# SCH_styresystemer_2026-04-27.net
KiCad netlist of a schematic drawn in EasyEDA
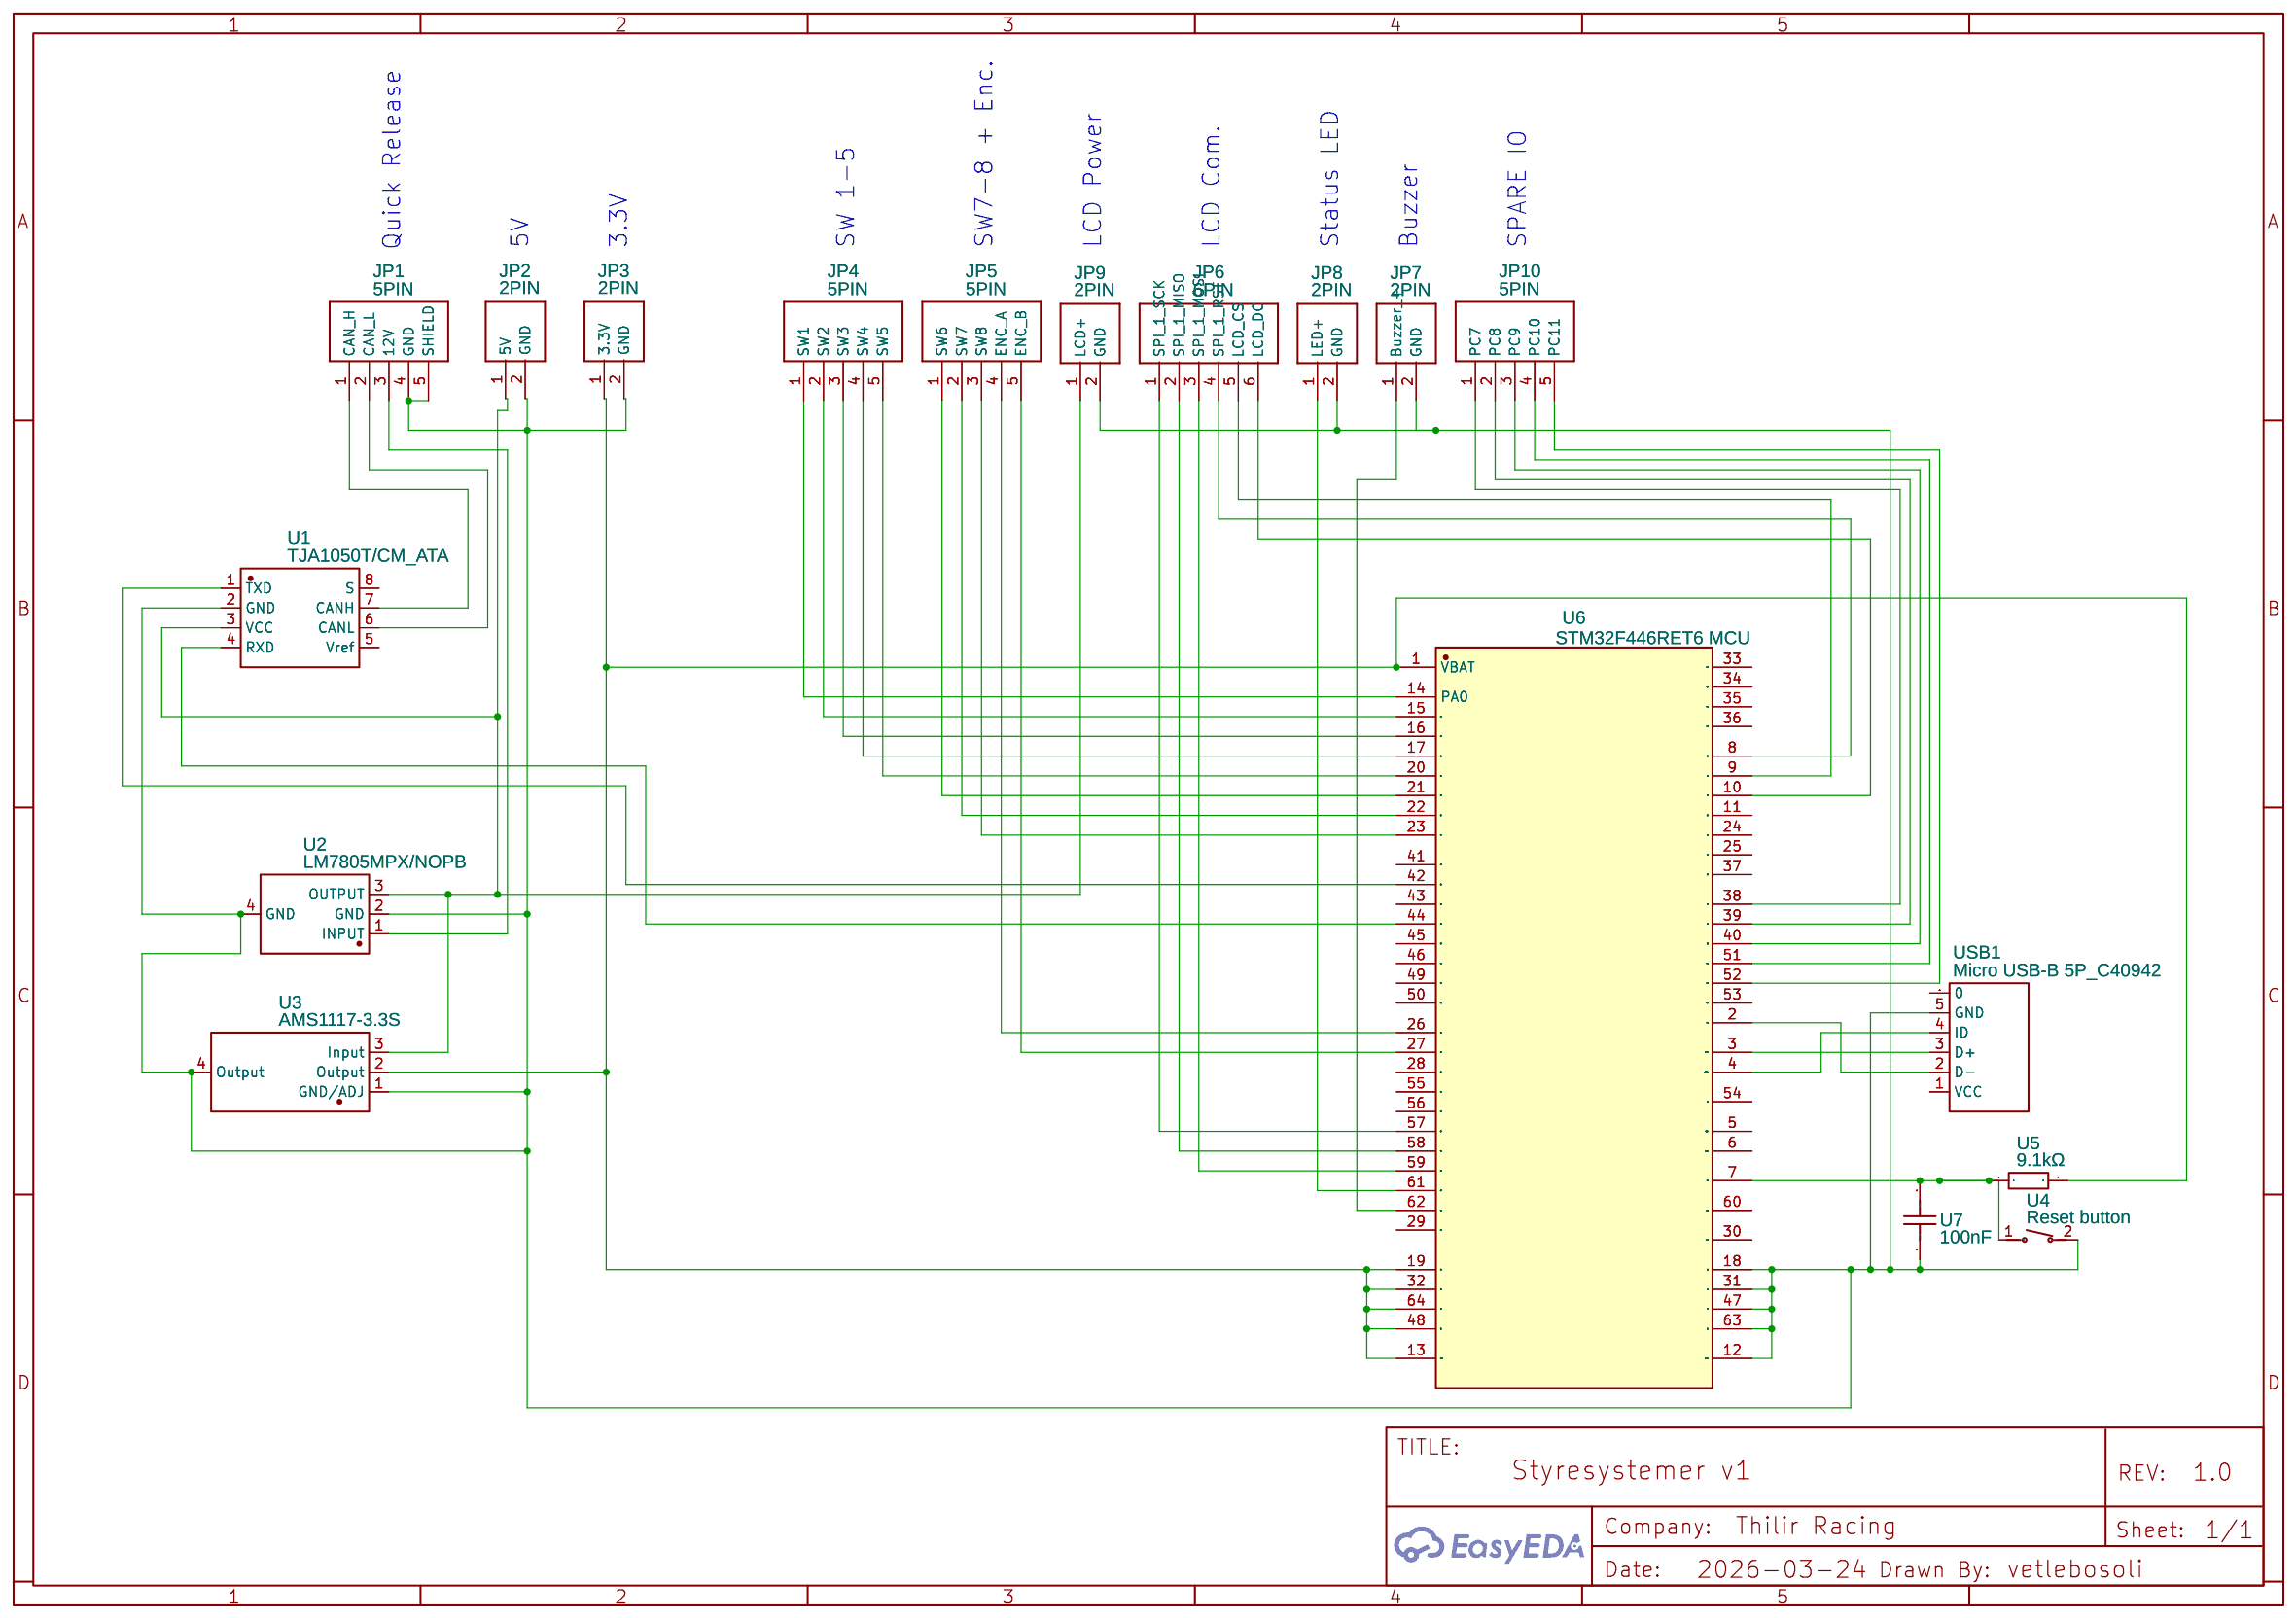
[diagram p0: schematic sheet]

(export (version "E")
  (design (tool "Eeschema 10.0.6"))
  (components
    (comp (ref "JP1") (value "5PIN") (libsource (lib "") (part "5PIN")))
    (comp (ref "JP2") (value "2PIN") (libsource (lib "") (part "2PIN_2")))
    (comp (ref "JP3") (value "2PIN") (libsource (lib "") (part "2PIN_4")))
    (comp (ref "JP4") (value "5PIN") (libsource (lib "") (part "5PIN_1")))
    (comp (ref "JP5") (value "5PIN") (libsource (lib "") (part "5PIN_3")))
    (comp (ref "JP6") (value "6PIN") (libsource (lib "") (part "6PIN")))
    (comp (ref "JP7") (value "2PIN") (libsource (lib "") (part "2PIN_3")))
    (comp (ref "JP8") (value "2PIN") (libsource (lib "") (part "2PIN")))
    (comp (ref "JP9") (value "2PIN") (libsource (lib "") (part "2PIN_1")))
    (comp (ref "JP10") (value "5PIN") (libsource (lib "") (part "5PIN_2")))
    (comp (ref "U1") (value "TJA1050T/CM_ATA") (libsource (lib "") (part "TJA1050T/CM_ATA")))
    (comp (ref "U2")
      (value "LM7805MPX/NOPB")
      (fields (field (name "Manufacturer") "TI(德州仪器)"))
      (libsource (lib "") (part "LM7805MPX/NOPB"))
    )
    (comp (ref "U3")
      (value "AMS1117-3.3S")
      (fields (field (name "Manufacturer") "KEXIN(科信)"))
      (libsource (lib "") (part "AMS1117-3.3S"))
    )
    (comp (ref "U4")
      (value "Reset button")
      (fields (field (name "Manufacturer Part") "BUTTON"))
      (libsource (lib "") (part "BUTTON_C9900040040"))
    )
    (comp (ref "U5")
      (value "9.1kΩ")
      (fields (field (name "Manufacturer Part") "HPCR0402F9K10K9") (field (name "Manufacturer") "RESI(开步睿思)"))
      (libsource (lib "") (part "HPCR0402F9K10K9"))
    )
    (comp (ref "U6")
      (value "STM32F446RET6 MCU")
      (fields
        (field (name "Manufacturer Part") "STM32F446RET6")
        (field (name "Manufacturer") "STMicroelectronics")
      )
      (libsource (lib "") (part "STM32F446RET6 MCU"))
    )
    (comp (ref "U7")
      (value "100nF")
      (fields (field (name "Manufacturer Part") "B32671P5104K000") (field (name "Manufacturer") "TDK"))
      (libsource (lib "") (part "B32671P5104K000"))
    )
    (comp (ref "USB1")
      (value "Micro USB-B 5P_C40942")
      (fields (field (name "Manufacturer Part") "920-D62A2021S10100") (field (name "Manufacturer") "精拓金"))
      (libsource (lib "") (part "Micro USB-B 5P_C40942"))
    )
  )
  (nets
    (net (code "1") (name "Net-(JP1-12V)") (class "Default")
      (node (ref "JP1") (pin "3") (pinfunction "12V_3") (pintype "unspecified"))
      (node (ref "U2") (pin "1") (pinfunction "INPUT_1") (pintype "unspecified"))
    )
    (net (code "2") (name "Net-(JP1-CAN_H)") (class "Default")
      (node (ref "JP1") (pin "1") (pinfunction "CAN_H_1") (pintype "unspecified"))
      (node (ref "U1") (pin "7") (pinfunction "CANH_7") (pintype "unspecified"))
    )
    (net (code "3") (name "Net-(JP1-CAN_L)") (class "Default")
      (node (ref "JP1") (pin "2") (pinfunction "CAN_L_2") (pintype "unspecified"))
      (node (ref "U1") (pin "6") (pinfunction "CANL_6") (pintype "unspecified"))
    )
    (net (code "4") (name "Net-(JP1-GND)") (class "Default")
      (node (ref "JP1") (pin "4") (pinfunction "GND_4") (pintype "unspecified"))
      (node (ref "JP1") (pin "5") (pinfunction "SHIELD_5") (pintype "unspecified"))
      (node (ref "JP2") (pin "2") (pinfunction "GND_2") (pintype "bidirectional"))
      (node (ref "JP3") (pin "2") (pinfunction "GND_2") (pintype "bidirectional"))
      (node (ref "JP7") (pin "2") (pinfunction "GND_2") (pintype "bidirectional"))
      (node (ref "JP8") (pin "2") (pinfunction "GND_2") (pintype "bidirectional"))
      (node (ref "JP9") (pin "2") (pinfunction "GND_2") (pintype "bidirectional"))
      (node (ref "U1") (pin "2") (pinfunction "GND_2") (pintype "unspecified"))
      (node (ref "U2") (pin "2") (pinfunction "GND_2") (pintype "unspecified"))
      (node (ref "U2") (pin "4") (pinfunction "GND_4") (pintype "unspecified"))
      (node (ref "U3") (pin "1") (pinfunction "GND/ADJ_1") (pintype "unspecified"))
      (node (ref "U3") (pin "4") (pinfunction "Output_4") (pintype "unspecified"))
      (node (ref "U4") (pin "2") (pinfunction "B_2") (pintype "unspecified"))
      (node (ref "U6") (pin "12") (pinfunction "VSSA/VREF-_12") (pintype "unspecified"))
      (node (ref "U6") (pin "18") (pinfunction "VSS_18") (pintype "unspecified"))
      (node (ref "U6") (pin "31") (pinfunction "VSS_31") (pintype "unspecified"))
      (node (ref "U6") (pin "47") (pinfunction "VSS_47") (pintype "unspecified"))
      (node (ref "U6") (pin "63") (pinfunction "VSS_63") (pintype "unspecified"))
      (node (ref "U7") (pin "1") (pinfunction "1_1") (pintype "unspecified"))
      (node (ref "USB1") (pin "5") (pinfunction "GND_5") (pintype "input"))
    )
    (net (code "5") (name "Net-(JP2-5V)") (class "Default")
      (node (ref "JP2") (pin "1") (pinfunction "5V_1") (pintype "bidirectional"))
      (node (ref "JP9") (pin "1") (pinfunction "LCD+_1") (pintype "bidirectional"))
      (node (ref "U1") (pin "3") (pinfunction "VCC_3") (pintype "unspecified"))
      (node (ref "U2") (pin "3") (pinfunction "OUTPUT_3") (pintype "unspecified"))
      (node (ref "U3") (pin "3") (pinfunction "Input_3") (pintype "unspecified"))
    )
    (net (code "6") (name "Net-(JP3-3.3V)") (class "Default")
      (node (ref "JP3") (pin "1") (pinfunction "3.3V_1") (pintype "bidirectional"))
      (node (ref "U3") (pin "2") (pinfunction "Output_2") (pintype "unspecified"))
      (node (ref "U5") (pin "2") (pinfunction "2_2") (pintype "unspecified"))
      (node (ref "U6") (pin "1") (pinfunction "VBAT_1") (pintype "unspecified"))
      (node (ref "U6") (pin "13") (pinfunction "VDDA/VREF+_13") (pintype "unspecified"))
      (node (ref "U6") (pin "19") (pinfunction "VDD_19") (pintype "unspecified"))
      (node (ref "U6") (pin "32") (pinfunction "VDD_32") (pintype "unspecified"))
      (node (ref "U6") (pin "48") (pinfunction "VDD_48") (pintype "unspecified"))
      (node (ref "U6") (pin "64") (pinfunction "VDD_64") (pintype "unspecified"))
    )
    (net (code "7") (name "Net-(JP4-SW1)") (class "Default")
      (node (ref "JP4") (pin "1") (pinfunction "SW1_1") (pintype "unspecified"))
      (node (ref "U6") (pin "14") (pinfunction "PA0_14") (pintype "unspecified"))
    )
    (net (code "8") (name "Net-(JP4-SW2)") (class "Default")
      (node (ref "JP4") (pin "2") (pinfunction "SW2_2") (pintype "unspecified"))
      (node (ref "U6") (pin "15") (pinfunction "PA1_15") (pintype "unspecified"))
    )
    (net (code "9") (name "Net-(JP4-SW3)") (class "Default")
      (node (ref "JP4") (pin "3") (pinfunction "SW3_3") (pintype "unspecified"))
      (node (ref "U6") (pin "16") (pinfunction "PA2_16") (pintype "unspecified"))
    )
    (net (code "10") (name "Net-(JP4-SW4)") (class "Default")
      (node (ref "JP4") (pin "4") (pinfunction "SW4_4") (pintype "unspecified"))
      (node (ref "U6") (pin "17") (pinfunction "PA3_17") (pintype "unspecified"))
    )
    (net (code "11") (name "Net-(JP4-SW5)") (class "Default")
      (node (ref "JP4") (pin "5") (pinfunction "SW5_5") (pintype "unspecified"))
      (node (ref "U6") (pin "20") (pinfunction "PA4_20") (pintype "unspecified"))
    )
    (net (code "12") (name "Net-(JP5-ENC_A)") (class "Default")
      (node (ref "JP5") (pin "4") (pinfunction "ENC_A_4") (pintype "unspecified"))
      (node (ref "U6") (pin "26") (pinfunction "PB0_26") (pintype "unspecified"))
    )
    (net (code "13") (name "Net-(JP5-ENC_B)") (class "Default")
      (node (ref "JP5") (pin "5") (pinfunction "ENC_B_5") (pintype "unspecified"))
      (node (ref "U6") (pin "27") (pinfunction "PB1_27") (pintype "unspecified"))
    )
    (net (code "14") (name "Net-(JP5-SW6)") (class "Default")
      (node (ref "JP5") (pin "1") (pinfunction "SW6_1") (pintype "unspecified"))
      (node (ref "U6") (pin "21") (pinfunction "PA5_21") (pintype "unspecified"))
    )
    (net (code "15") (name "Net-(JP5-SW7)") (class "Default")
      (node (ref "JP5") (pin "2") (pinfunction "SW7_2") (pintype "unspecified"))
      (node (ref "U6") (pin "22") (pinfunction "PA6_22") (pintype "unspecified"))
    )
    (net (code "16") (name "Net-(JP5-SW8)") (class "Default")
      (node (ref "JP5") (pin "3") (pinfunction "SW8_3") (pintype "unspecified"))
      (node (ref "U6") (pin "23") (pinfunction "PA7_23") (pintype "unspecified"))
    )
    (net (code "17") (name "Net-(JP6-LCD_CS)") (class "Default")
      (node (ref "JP6") (pin "5") (pinfunction "LCD_CS_5") (pintype "bidirectional"))
      (node (ref "U6") (pin "9") (pinfunction "PC1_9") (pintype "unspecified"))
    )
    (net (code "18") (name "Net-(JP6-LCD_DC)") (class "Default")
      (node (ref "JP6") (pin "6") (pinfunction "LCD_DC_6") (pintype "bidirectional"))
      (node (ref "U6") (pin "10") (pinfunction "PC2_10") (pintype "unspecified"))
    )
    (net (code "19") (name "Net-(JP6-SPI_1_MISO)") (class "Default")
      (node (ref "JP6") (pin "2") (pinfunction "SPI_1_MISO_2") (pintype "bidirectional"))
      (node (ref "U6") (pin "58") (pinfunction "PB6_58") (pintype "unspecified"))
    )
    (net (code "20") (name "Net-(JP6-SPI_1_MOSI)") (class "Default")
      (node (ref "JP6") (pin "3") (pinfunction "SPI_1_MOSI_3") (pintype "bidirectional"))
      (node (ref "U6") (pin "59") (pinfunction "PB7_59") (pintype "unspecified"))
    )
    (net (code "21") (name "Net-(JP6-SPI_1_RST)") (class "Default")
      (node (ref "JP6") (pin "4") (pinfunction "SPI_1_RST_4") (pintype "bidirectional"))
      (node (ref "U6") (pin "8") (pinfunction "PC0_8") (pintype "unspecified"))
    )
    (net (code "22") (name "Net-(JP6-SPI_1_SCK)") (class "Default")
      (node (ref "JP6") (pin "1") (pinfunction "SPI_1_SCK_1") (pintype "bidirectional"))
      (node (ref "U6") (pin "57") (pinfunction "PB5_57") (pintype "unspecified"))
    )
    (net (code "23") (name "Net-(JP7-Buzzer_+)") (class "Default")
      (node (ref "JP7") (pin "1") (pinfunction "Buzzer_+_1") (pintype "bidirectional"))
      (node (ref "U6") (pin "62") (pinfunction "PB9_62") (pintype "unspecified"))
    )
    (net (code "24") (name "Net-(JP8-LED+)") (class "Default")
      (node (ref "JP8") (pin "1") (pinfunction "LED+_1") (pintype "bidirectional"))
      (node (ref "U6") (pin "61") (pinfunction "PB8_61") (pintype "unspecified"))
    )
    (net (code "25") (name "Net-(JP10-PC7)") (class "Default")
      (node (ref "JP10") (pin "1") (pinfunction "PC7_1") (pintype "unspecified"))
      (node (ref "U6") (pin "38") (pinfunction "PC7_38") (pintype "unspecified"))
    )
    (net (code "26") (name "Net-(JP10-PC8)") (class "Default")
      (node (ref "JP10") (pin "2") (pinfunction "PC8_2") (pintype "unspecified"))
      (node (ref "U6") (pin "39") (pinfunction "PC8_39") (pintype "unspecified"))
    )
    (net (code "27") (name "Net-(JP10-PC9)") (class "Default")
      (node (ref "JP10") (pin "3") (pinfunction "PC9_3") (pintype "unspecified"))
      (node (ref "U6") (pin "40") (pinfunction "PC9_40") (pintype "unspecified"))
    )
    (net (code "28") (name "Net-(JP10-PC10)") (class "Default")
      (node (ref "JP10") (pin "4") (pinfunction "PC10_4") (pintype "unspecified"))
      (node (ref "U6") (pin "51") (pinfunction "PC10_51") (pintype "unspecified"))
    )
    (net (code "29") (name "Net-(JP10-PC11)") (class "Default")
      (node (ref "JP10") (pin "5") (pinfunction "PC11_5") (pintype "unspecified"))
      (node (ref "U6") (pin "52") (pinfunction "PC11_52") (pintype "unspecified"))
    )
    (net (code "30") (name "Net-(U1-RXD)") (class "Default")
      (node (ref "U1") (pin "4") (pinfunction "RXD_4") (pintype "unspecified"))
      (node (ref "U6") (pin "44") (pinfunction "PA11_44") (pintype "unspecified"))
    )
    (net (code "31") (name "Net-(U1-TXD)") (class "Default")
      (node (ref "U1") (pin "1") (pinfunction "TXD_1") (pintype "unspecified"))
      (node (ref "U6") (pin "42") (pinfunction "PA9_42") (pintype "unspecified"))
    )
    (net (code "32") (name "Net-(U4-A)") (class "Default")
      (node (ref "U4") (pin "1") (pinfunction "A_1") (pintype "unspecified"))
      (node (ref "U5") (pin "1") (pinfunction "1_1") (pintype "unspecified"))
      (node (ref "U6") (pin "7") (pinfunction "NRST_7") (pintype "unspecified"))
      (node (ref "U7") (pin "2") (pinfunction "2_2") (pintype "unspecified"))
    )
    (net (code "33") (name "Net-(U6-PC13)") (class "Default")
      (node (ref "U6") (pin "2") (pinfunction "PC13_2") (pintype "unspecified"))
      (node (ref "USB1") (pin "2") (pinfunction "D-_2") (pintype "input"))
    )
    (net (code "34") (name "Net-(U6-PC14-OSC32_IN)") (class "Default")
      (node (ref "U6") (pin "3") (pinfunction "PC14-OSC32_IN_3") (pintype "unspecified"))
      (node (ref "USB1") (pin "3") (pinfunction "D+_3") (pintype "input"))
    )
    (net (code "35") (name "Net-(U6-PC15-OSC32_OUT)") (class "Default")
      (node (ref "U6") (pin "4") (pinfunction "PC15-OSC32_OUT_4") (pintype "unspecified"))
      (node (ref "USB1") (pin "4") (pinfunction "ID_4") (pintype "input"))
    )
    (net (code "36") (name "unconnected-(U1-S-Pad8)") (class "Default")
      (node (ref "U1") (pin "8") (pinfunction "S_8") (pintype "unspecified"))
    )
    (net (code "37") (name "unconnected-(U1-Vref-Pad5)") (class "Default")
      (node (ref "U1") (pin "5") (pinfunction "Vref_5") (pintype "unspecified"))
    )
    (net (code "38") (name "unconnected-(U6-BOOT0-Pad60)") (class "Default")
      (node (ref "U6") (pin "60") (pinfunction "BOOT0_60") (pintype "unspecified"))
    )
    (net (code "39") (name "unconnected-(U6-PA8-Pad41)") (class "Default")
      (node (ref "U6") (pin "41") (pinfunction "PA8_41") (pintype "unspecified"))
    )
    (net (code "40") (name "unconnected-(U6-PA10-Pad43)") (class "Default")
      (node (ref "U6") (pin "43") (pinfunction "PA10_43") (pintype "unspecified"))
    )
    (net (code "41") (name "unconnected-(U6-PA12-Pad45)") (class "Default")
      (node (ref "U6") (pin "45") (pinfunction "PA12_45") (pintype "unspecified"))
    )
    (net (code "42") (name "unconnected-(U6-PA13-Pad46)") (class "Default")
      (node (ref "U6") (pin "46") (pinfunction "PA13_46") (pintype "unspecified"))
    )
    (net (code "43") (name "unconnected-(U6-PA14-Pad49)") (class "Default")
      (node (ref "U6") (pin "49") (pinfunction "PA14_49") (pintype "unspecified"))
    )
    (net (code "44") (name "unconnected-(U6-PA15-Pad50)") (class "Default")
      (node (ref "U6") (pin "50") (pinfunction "PA15_50") (pintype "unspecified"))
    )
    (net (code "45") (name "unconnected-(U6-PB2-Pad28)") (class "Default")
      (node (ref "U6") (pin "28") (pinfunction "PB2_28") (pintype "unspecified"))
    )
    (net (code "46") (name "unconnected-(U6-PB3-Pad55)") (class "Default")
      (node (ref "U6") (pin "55") (pinfunction "PB3_55") (pintype "unspecified"))
    )
    (net (code "47") (name "unconnected-(U6-PB4-Pad56)") (class "Default")
      (node (ref "U6") (pin "56") (pinfunction "PB4_56") (pintype "unspecified"))
    )
    (net (code "48") (name "unconnected-(U6-PB10-Pad29)") (class "Default")
      (node (ref "U6") (pin "29") (pinfunction "PB10_29") (pintype "unspecified"))
    )
    (net (code "49") (name "unconnected-(U6-PB12-Pad33)") (class "Default")
      (node (ref "U6") (pin "33") (pinfunction "PB12_33") (pintype "unspecified"))
    )
    (net (code "50") (name "unconnected-(U6-PB13-Pad34)") (class "Default")
      (node (ref "U6") (pin "34") (pinfunction "PB13_34") (pintype "unspecified"))
    )
    (net (code "51") (name "unconnected-(U6-PB14-Pad35)") (class "Default")
      (node (ref "U6") (pin "35") (pinfunction "PB14_35") (pintype "unspecified"))
    )
    (net (code "52") (name "unconnected-(U6-PB15-Pad36)") (class "Default")
      (node (ref "U6") (pin "36") (pinfunction "PB15_36") (pintype "unspecified"))
    )
    (net (code "53") (name "unconnected-(U6-PC3-Pad11)") (class "Default")
      (node (ref "U6") (pin "11") (pinfunction "PC3_11") (pintype "unspecified"))
    )
    (net (code "54") (name "unconnected-(U6-PC4-Pad24)") (class "Default")
      (node (ref "U6") (pin "24") (pinfunction "PC4_24") (pintype "unspecified"))
    )
    (net (code "55") (name "unconnected-(U6-PC5-Pad25)") (class "Default")
      (node (ref "U6") (pin "25") (pinfunction "PC5_25") (pintype "unspecified"))
    )
    (net (code "56") (name "unconnected-(U6-PC6-Pad37)") (class "Default")
      (node (ref "U6") (pin "37") (pinfunction "PC6_37") (pintype "unspecified"))
    )
    (net (code "57") (name "unconnected-(U6-PC12-Pad53)") (class "Default")
      (node (ref "U6") (pin "53") (pinfunction "PC12_53") (pintype "unspecified"))
    )
    (net (code "58") (name "unconnected-(U6-PD2-Pad54)") (class "Default")
      (node (ref "U6") (pin "54") (pinfunction "PD2_54") (pintype "unspecified"))
    )
    (net (code "59") (name "unconnected-(U6-PH0-OSC_IN-Pad5)") (class "Default")
      (node (ref "U6") (pin "5") (pinfunction "PH0-OSC_IN_5") (pintype "unspecified"))
    )
    (net (code "60") (name "unconnected-(U6-PH1-OSC_OUT-Pad6)") (class "Default")
      (node (ref "U6") (pin "6") (pinfunction "PH1-OSC_OUT_6") (pintype "unspecified"))
    )
    (net (code "61") (name "unconnected-(U6-VCAP_1-Pad30)") (class "Default")
      (node (ref "U6") (pin "30") (pinfunction "VCAP_1_30") (pintype "unspecified"))
    )
    (net (code "62") (name "unconnected-(USB1-Pad0)") (class "Default")
      (node (ref "USB1") (pin "0") (pinfunction "0_0") (pintype "input"))
    )
    (net (code "63") (name "unconnected-(USB1-VCC-Pad1)") (class "Default")
      (node (ref "USB1") (pin "1") (pinfunction "VCC_1") (pintype "input"))
    )
  )
)
